# LAN9254_C_P1.net
KiCad netlist of a schematic drawn in Altium Designer
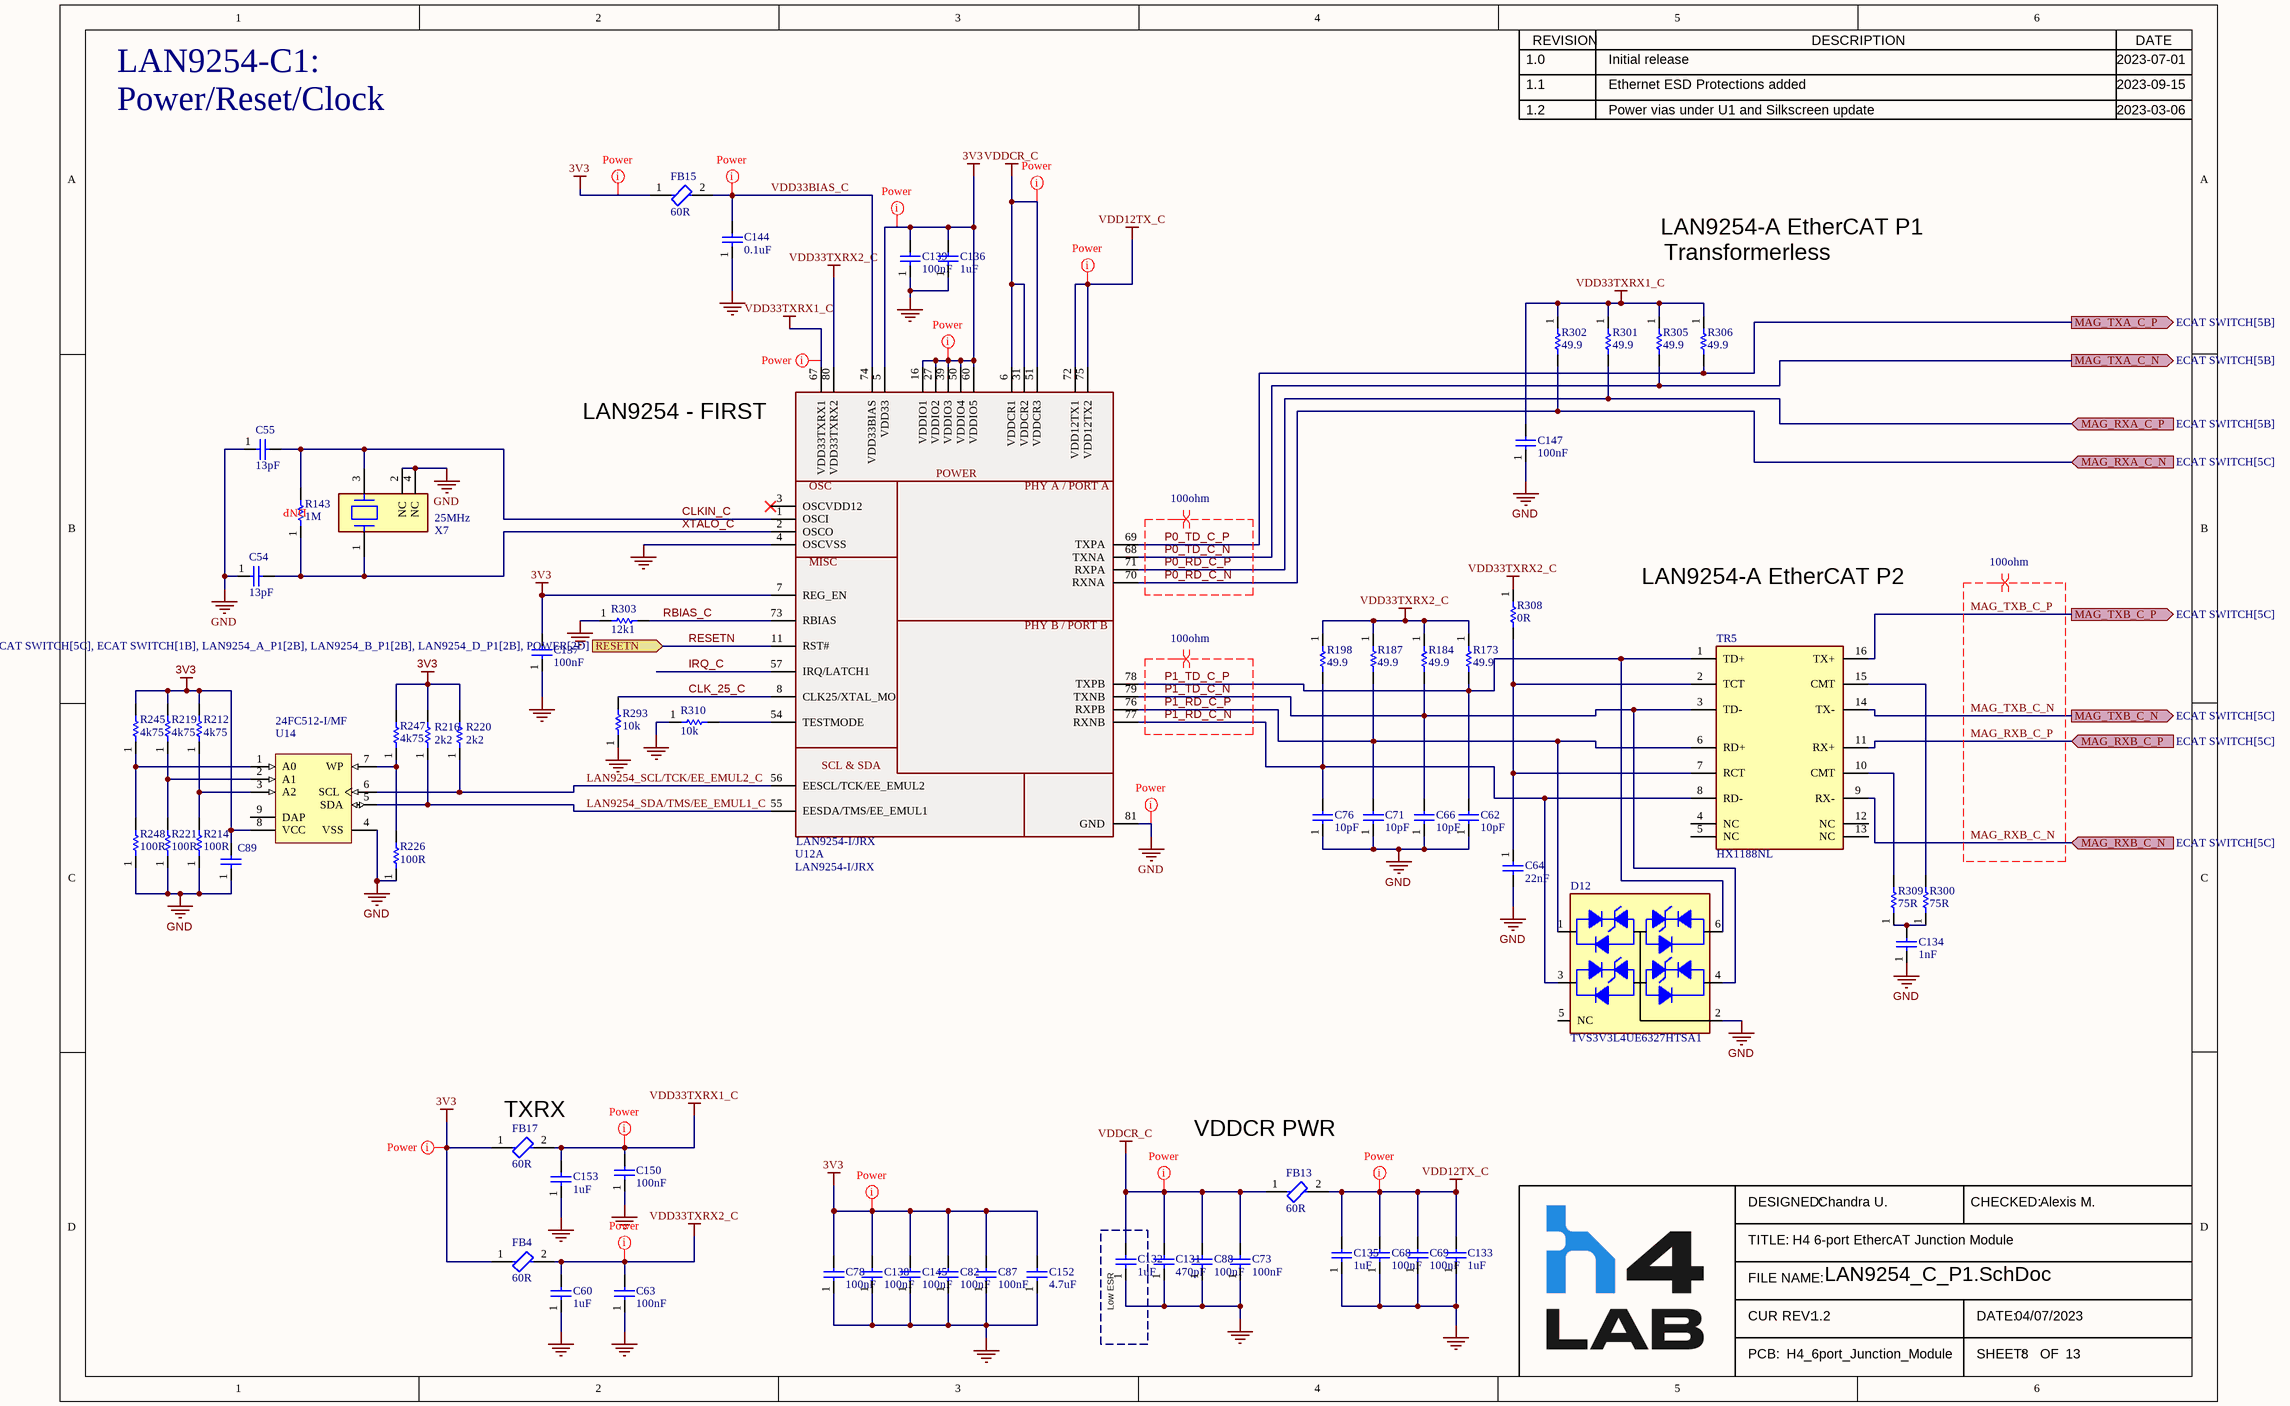
[diagram p0: LAN9254_C_P1.SchDoc]

(export (version "E")
  (design (tool "Eeschema 10.0.6"))
  (components
    (comp (ref "C54")
      (value "13pF")
      (footprint "0402_C")
      (description "Cap Ceramic Monolithic 13pF 50VDC 2% SMD Emboss T/R")
      (fields
        (field (name "MANUFACTURER") "Murata")
        (field (name "MANUFACTURER PART NUMBER") "GRM0225C1H130GA03L")
      )
      (libsource (lib "IHMC_Capacitors") (part "13pF_50V_0402_CAP_GRM0225C1H130GA03L"))
    )
    (comp (ref "C55")
      (value "13pF")
      (footprint "0402_C")
      (description "Cap Ceramic Monolithic 13pF 50VDC 2% SMD Emboss T/R")
      (fields
        (field (name "MANUFACTURER") "Murata")
        (field (name "MANUFACTURER PART NUMBER") "GRM0225C1H130GA03L")
      )
      (libsource (lib "IHMC_Capacitors") (part "13pF_50V_0402_CAP_GRM0225C1H130GA03L"))
    )
    (comp (ref "C60")
      (value "1uF")
      (footprint "CAPC1608X09N(0603)")
      (description "MLCC - SMD/SMT 25volts 1uF X5R 10%")
      (fields
        (field (name "MPN") "C0603C105K3PACTU")
        (field (name "VOLTAGE") "25VDC")
        (field (name "DRAWN BY") "TC")
      )
      (libsource (lib "IHMC_Altium_Lib") (part "1uF_25VDC_0603_Cap"))
    )
    (comp (ref "C62")
      (value "10pF")
      (footprint "0402_C")
      (description "Cap Ceramic 10pF 50V C0G 5% SMD 0402 125°C Punched Paper T/R")
      (fields (field (name "TOLERANCE") "5%") (field (name "MANUFACTURER") "KEMET"))
      (libsource (lib "IHMC_Altium_Lib") (part "10pF_50V_0402_C0402C100J5GAC7411"))
    )
    (comp (ref "C63")
      (value "100nF")
      (footprint "CAPC1005X03N(0402)")
      (description "CAP CER 0.1UF 16V X7R 0402")
      (fields (field (name "MPN") "GRM155R71C104JA88D") (field (name "TOLERANCE") "5%"))
      (libsource (lib "IHMC_Altium_Lib") (part "100nF_16V_0402_CAP"))
    )
    (comp (ref "C64")
      (value "22nF")
      (footprint "CAPC1005X03N(0402)")
      (description "CAP CER 0.022UF 50V X7R 0402")
      (fields (field (name "MPN") "GCM155R71H223KA55D") (field (name "TOLERANCE") "10%"))
      (libsource (lib "IHMC_Capacitors") (part "22nF_50V_0402_CAP"))
    )
    (comp (ref "C66")
      (value "10pF")
      (footprint "0402_C")
      (description "Cap Ceramic 10pF 50V C0G 5% SMD 0402 125°C Punched Paper T/R")
      (fields (field (name "TOLERANCE") "5%") (field (name "MANUFACTURER") "KEMET"))
      (libsource (lib "IHMC_Altium_Lib") (part "10pF_50V_0402_C0402C100J5GAC7411"))
    )
    (comp (ref "C68")
      (value "100nF")
      (footprint "CAPC1005X03N(0402)")
      (description "CAP CER 0.1UF 16V X7R 0402")
      (fields (field (name "MPN") "GRM155R71C104JA88D") (field (name "TOLERANCE") "5%"))
      (libsource (lib "IHMC_Altium_Lib") (part "100nF_16V_0402_CAP"))
    )
    (comp (ref "C69")
      (value "100nF")
      (footprint "CAPC1005X03N(0402)")
      (description "CAP CER 0.1UF 16V X7R 0402")
      (fields (field (name "MPN") "GRM155R71C104JA88D") (field (name "TOLERANCE") "5%"))
      (libsource (lib "IHMC_Altium_Lib") (part "100nF_16V_0402_CAP"))
    )
    (comp (ref "C71")
      (value "10pF")
      (footprint "0402_C")
      (description "Cap Ceramic 10pF 50V C0G 5% SMD 0402 125°C Punched Paper T/R")
      (fields (field (name "TOLERANCE") "5%") (field (name "MANUFACTURER") "KEMET"))
      (libsource (lib "IHMC_Altium_Lib") (part "10pF_50V_0402_C0402C100J5GAC7411"))
    )
    (comp (ref "C73")
      (value "100nF")
      (footprint "CAPC1005X03N(0402)")
      (description "CAP CER 0.1UF 16V X7R 0402")
      (fields (field (name "MPN") "GRM155R71C104JA88D") (field (name "TOLERANCE") "5%"))
      (libsource (lib "IHMC_Altium_Lib") (part "100nF_16V_0402_CAP"))
    )
    (comp (ref "C76")
      (value "10pF")
      (footprint "0402_C")
      (description "Cap Ceramic 10pF 50V C0G 5% SMD 0402 125°C Punched Paper T/R")
      (fields (field (name "TOLERANCE") "5%") (field (name "MANUFACTURER") "KEMET"))
      (libsource (lib "IHMC_Altium_Lib") (part "10pF_50V_0402_C0402C100J5GAC7411"))
    )
    (comp (ref "C78")
      (value "100nF")
      (footprint "CAPC1005X03N(0402)")
      (description "CAP CER 0.1UF 16V X7R 0402")
      (fields (field (name "MPN") "GRM155R71C104JA88D") (field (name "TOLERANCE") "5%"))
      (libsource (lib "IHMC_Altium_Lib") (part "100nF_16V_0402_CAP"))
    )
    (comp (ref "C82")
      (value "100nF")
      (footprint "CAPC1005X03N(0402)")
      (description "CAP CER 0.1UF 16V X7R 0402")
      (fields (field (name "MPN") "GRM155R71C104JA88D") (field (name "TOLERANCE") "5%"))
      (libsource (lib "IHMC_Altium_Lib") (part "100nF_16V_0402_CAP"))
    )
    (comp (ref "C87")
      (value "100nF")
      (footprint "CAPC1005X03N(0402)")
      (description "CAP CER 0.1UF 16V X7R 0402")
      (fields (field (name "MPN") "GRM155R71C104JA88D") (field (name "TOLERANCE") "5%"))
      (libsource (lib "IHMC_Altium_Lib") (part "100nF_16V_0402_CAP"))
    )
    (comp (ref "C88")
      (value "100nF")
      (footprint "CAPC1005X03N(0402)")
      (description "CAP CER 0.1UF 16V X7R 0402")
      (fields (field (name "MPN") "GRM155R71C104JA88D") (field (name "TOLERANCE") "5%"))
      (libsource (lib "IHMC_Altium_Lib") (part "100nF_16V_0402_CAP"))
    )
    (comp (ref "C89")
      (value "GRM155R71C104JA88D")
      (footprint "CAPC1005X03N(0402)")
      (description "CAP CER 0.1UF 16V X7R 0402")
      (fields (field (name "TOLERANCE") "5%"))
      (libsource (lib "IHMC_Altium_Lib") (part "100nF_16V_0402_CAP"))
    )
    (comp (ref "C131")
      (value "470pF")
      (footprint "CAPC1005X03N(0402)")
      (description "CAP CER 470PF 50V C0G/NP0 0402")
      (fields (field (name "MPN") "GCM1555C1H471JA16D") (field (name "VOLTAGE") "50V"))
      (libsource (lib "IHMC_Altium_Lib") (part "470pF_50V_0402_CAP"))
    )
    (comp (ref "C132")
      (value "1uF")
      (footprint "0603_C")
      (description "Multilayer Ceramic Capacitors (High dielectric type), 10V, 1 uF, ± 10 %, 0603, X5R, RoHS")
      (fields (field (name "TOLERANCE") "10%") (field (name "MANUFACTURER") "Taiyo Yuden"))
      (libsource (lib "IHMC_Capacitors") (part "1uF_10V_low_ESR_0603_LMK107BJ105KA-T"))
    )
    (comp (ref "C133")
      (value "1uF")
      (footprint "CAPC1608X09N(0603)")
      (description "MLCC - SMD/SMT 25volts 1uF X5R 10%")
      (fields
        (field (name "MPN") "C0603C105K3PACTU")
        (field (name "VOLTAGE") "25VDC")
        (field (name "DRAWN BY") "TC")
      )
      (libsource (lib "IHMC_Altium_Lib") (part "1uF_25VDC_0603_Cap"))
    )
    (comp (ref "C134")
      (value "1nF")
      (footprint "CAPC3216X16N(1206)")
      (description "CAP CER 1000PF 2KV X7R 1206")
      (fields (field (name "TOLERANCE") "10%") (field (name "MPN") "CC1206KKX7RDBB102"))
      (libsource (lib "IHMC_Altium_Lib") (part "1nF_2kV_1206_CAP"))
    )
    (comp (ref "C135")
      (value "1uF")
      (footprint "CAPC1608X09N(0603)")
      (description "MLCC - SMD/SMT 25volts 1uF X5R 10%")
      (fields
        (field (name "MPN") "C0603C105K3PACTU")
        (field (name "VOLTAGE") "25VDC")
        (field (name "DRAWN BY") "TC")
      )
      (libsource (lib "IHMC_Altium_Lib") (part "1uF_25VDC_0603_Cap"))
    )
    (comp (ref "C136")
      (value "1uF")
      (footprint "0603_C")
      (description "Multilayer Ceramic Capacitors (High dielectric type), 10V, 1 uF, ± 10 %, 0603, X5R, RoHS")
      (fields (field (name "TOLERANCE") "10%") (field (name "MANUFACTURER") "Taiyo Yuden"))
      (libsource (lib "IHMC_Capacitors") (part "1uF_10V_low_ESR_0603_LMK107BJ105KA-T"))
    )
    (comp (ref "C137")
      (value "100nF")
      (footprint "CAPC1005X03N(0402)")
      (description "CAP CER 0.1UF 16V X7R 0402")
      (fields (field (name "MPN") "GRM155R71C104JA88D") (field (name "TOLERANCE") "5%"))
      (libsource (lib "IHMC_Altium_Lib") (part "100nF_16V_0402_CAP"))
    )
    (comp (ref "C138")
      (value "100nF")
      (footprint "CAPC1005X03N(0402)")
      (description "CAP CER 0.1UF 16V X7R 0402")
      (fields (field (name "MPN") "GRM155R71C104JA88D") (field (name "TOLERANCE") "5%"))
      (libsource (lib "IHMC_Altium_Lib") (part "100nF_16V_0402_CAP"))
    )
    (comp (ref "C139")
      (value "100nF")
      (footprint "CAPC1005X03N(0402)")
      (description "CAP CER 0.1UF 16V X7R 0402")
      (fields (field (name "MPN") "GRM155R71C104JA88D") (field (name "TOLERANCE") "5%"))
      (libsource (lib "IHMC_Altium_Lib") (part "100nF_16V_0402_CAP"))
    )
    (comp (ref "C144")
      (value "0.1uF")
      (footprint "CAPC1608X09N(0603)")
      (description "CAP CER 0.1UF 100V X7R 0603")
      (fields (field (name "MPN") "CL10B104KC8NNNC") (field (name "TOLERANCE") "10%"))
      (libsource (lib "IHMC_Altium_Lib") (part "0.1uF_100V_0603_CAP"))
    )
    (comp (ref "C145")
      (value "100nF")
      (footprint "CAPC1005X03N(0402)")
      (description "CAP CER 0.1UF 16V X7R 0402")
      (fields (field (name "MPN") "GRM155R71C104JA88D") (field (name "TOLERANCE") "5%"))
      (libsource (lib "IHMC_Altium_Lib") (part "100nF_16V_0402_CAP"))
    )
    (comp (ref "C147")
      (value "100nF")
      (footprint "CAPC1005X03N(0402)")
      (description "CAP CER 0.1UF 16V X7R 0402")
      (fields (field (name "TOLERANCE") "5%") (field (name "MPN") "GRM155R71C104JA88D"))
      (libsource (lib "IHMC_Altium_Lib") (part "100nF_16V_0402_CAP"))
    )
    (comp (ref "C150")
      (value "100nF")
      (footprint "CAPC1005X03N(0402)")
      (description "CAP CER 0.1UF 16V X7R 0402")
      (fields (field (name "MPN") "GRM155R71C104JA88D") (field (name "TOLERANCE") "5%"))
      (libsource (lib "IHMC_Altium_Lib") (part "100nF_16V_0402_CAP"))
    )
    (comp (ref "C152")
      (value "4.7uF")
      (footprint "CAPC3216X16N(1206)")
      (description "CAP CER 4.7UF 50V X7R 1206")
      (fields (field (name "MPN") "CL31B475KBHNNNE") (field (name "TOLERANCE") "10%"))
      (libsource (lib "IHMC_Altium_Lib") (part "4.7uF_50V_1206_CAP"))
    )
    (comp (ref "C153")
      (value "1uF")
      (footprint "CAPC1608X09N(0603)")
      (description "MLCC - SMD/SMT 25volts 1uF X5R 10%")
      (fields
        (field (name "MPN") "C0603C105K3PACTU")
        (field (name "VOLTAGE") "25VDC")
        (field (name "DRAWN BY") "TC")
      )
      (libsource (lib "IHMC_Altium_Lib") (part "1uF_25VDC_0603_Cap"))
    )
    (comp (ref "D12")
      (value "TVS3V3L4UE6327HTSA1")
      (footprint "FP-SOT457-MFG")
      (description "Trans Voltage Suppressor Diode, 3.3V V(RWM), Unidirectional, 4 Element, Silicon")
      (fields (field (name "MANUFACTURER") "Infineon"))
      (libsource (lib "IHMC_Altium_Lib") (part "TVS_DIODE_ETHERCAT_PHY_7.7V_20A_TVS3V3L4UE6327HTSA1"))
    )
    (comp (ref "FB4")
      (value "BKP2125HS600-T")
      (footprint "FP-BKP2125-IPC_C")
      (fields
        (field (name "TOLERANCE") "25%")
        (field (name "MANUFACTURER") "Taiyo Yuden")
        (field (name "IMPEDANCE") "60R")
      )
      (libsource (lib "IHMC_Altium_Lib") (part "60R_100Mhz_0805_3A"))
    )
    (comp (ref "FB13")
      (value "BKP2125HS600-T")
      (footprint "FP-BKP2125-IPC_C")
      (fields
        (field (name "TOLERANCE") "25%")
        (field (name "MANUFACTURER") "Taiyo Yuden")
        (field (name "IMPEDANCE") "60R")
      )
      (libsource (lib "IHMC_Altium_Lib") (part "60R_100Mhz_0805_3A"))
    )
    (comp (ref "FB15")
      (value "BKP2125HS600-T")
      (footprint "FP-BKP2125-IPC_C")
      (fields
        (field (name "TOLERANCE") "25%")
        (field (name "MANUFACTURER") "Taiyo Yuden")
        (field (name "IMPEDANCE") "60R")
      )
      (libsource (lib "IHMC_Altium_Lib") (part "60R_100Mhz_0805_3A"))
    )
    (comp (ref "FB17")
      (value "BKP2125HS600-T")
      (footprint "FP-BKP2125-IPC_C")
      (fields
        (field (name "TOLERANCE") "25%")
        (field (name "MANUFACTURER") "Taiyo Yuden")
        (field (name "IMPEDANCE") "60R")
      )
      (libsource (lib "IHMC_Altium_Lib") (part "60R_100Mhz_0805_3A"))
    )
    (comp (ref "R143")
      (value "1M")
      (footprint "RESC1608X09N(0603)")
      (description "RES SMD 1M OHM 1% 1/10W 0603")
      (fields (field (name "MPN") "RC0603FR-071ML") (field (name "TOLERANCE") "1%"))
      (libsource (lib "IHMC_Altium_Lib") (part "1M_1/10W_RES_0603"))
    )
    (comp (ref "R173")
      (value "49.9")
      (footprint "RESC1005X06N(0402)")
      (description "RES SMD 49.9 OHM 1% 1/16W 0402")
      (fields
        (field (name "MPN") "CRCW040249R9FKED")
        (field (name "TOLERANCE") "1%")
        (field (name "DRAWN BY") "TC")
      )
      (libsource (lib "IHMC_Altium_Lib") (part "49R9_1/10W_0402_RES"))
    )
    (comp (ref "R184")
      (value "49.9")
      (footprint "RESC1005X06N(0402)")
      (description "RES SMD 49.9 OHM 1% 1/16W 0402")
      (fields
        (field (name "MPN") "CRCW040249R9FKED")
        (field (name "TOLERANCE") "1%")
        (field (name "DRAWN BY") "TC")
      )
      (libsource (lib "IHMC_Altium_Lib") (part "49R9_1/10W_0402_RES"))
    )
    (comp (ref "R187")
      (value "49.9")
      (footprint "RESC1005X06N(0402)")
      (description "RES SMD 49.9 OHM 1% 1/16W 0402")
      (fields
        (field (name "MPN") "CRCW040249R9FKED")
        (field (name "TOLERANCE") "1%")
        (field (name "DRAWN BY") "TC")
      )
      (libsource (lib "IHMC_Altium_Lib") (part "49R9_1/10W_0402_RES"))
    )
    (comp (ref "R198")
      (value "49.9")
      (footprint "RESC1005X06N(0402)")
      (description "RES SMD 49.9 OHM 1% 1/16W 0402")
      (fields
        (field (name "MPN") "CRCW040249R9FKED")
        (field (name "TOLERANCE") "1%")
        (field (name "DRAWN BY") "TC")
      )
      (libsource (lib "IHMC_Altium_Lib") (part "49R9_1/10W_0402_RES"))
    )
    (comp (ref "R212")
      (value "4k75")
      (footprint "RESC1005X06N(0402)")
      (description "RES SMD 4.75K OHM 1% 1/16W 0402")
      (fields (field (name "MPN") "RC0402FR-074K75L") (field (name "POWER") "1/16"))
      (libsource (lib "IHMC_Altium_Lib") (part "4k75_1/16_0402_RES"))
    )
    (comp (ref "R214")
      (value "100R")
      (footprint "0402")
      (description "Res Thick Film 0402 100 Ohm 1% 0.063W(1/16W) ±200ppm/C Pad SMD Automotive T/R")
      (fields
        (field (name "MANUFACTURER") "TE Connectivity")
        (field (name "MANUFACTURER PART NUMBER") "CRGCQ0402F100R")
      )
      (libsource (lib "IHMC_Altium_Lib") (part "100R_1/16_0402_RES"))
    )
    (comp (ref "R216")
      (value "2k2")
      (footprint "0402")
      (description "Vishay CRCW Series Thick Film Resistor 0402 Case 2.2k 5% 0.063W 200ppm/K")
      (fields (field (name "TOLERANCE") "5%") (field (name "MANUFACTURER") "Vishay Dale"))
      (libsource (lib "IHMC_Altium_Lib") (part "2k2_1/16_0402_CRCW04022K20JNED_RES"))
    )
    (comp (ref "R219")
      (value "4k75")
      (footprint "RESC1005X06N(0402)")
      (description "RES SMD 4.75K OHM 1% 1/16W 0402")
      (fields (field (name "MPN") "RC0402FR-074K75L") (field (name "POWER") "1/16"))
      (libsource (lib "IHMC_Altium_Lib") (part "4k75_1/16_0402_RES"))
    )
    (comp (ref "R220")
      (value "2k2")
      (footprint "0402")
      (description "Vishay CRCW Series Thick Film Resistor 0402 Case 2.2k 5% 0.063W 200ppm/K")
      (fields (field (name "TOLERANCE") "5%") (field (name "MANUFACTURER") "Vishay Dale"))
      (libsource (lib "IHMC_Altium_Lib") (part "2k2_1/16_0402_CRCW04022K20JNED_RES"))
    )
    (comp (ref "R221")
      (value "100R")
      (footprint "0402")
      (description "Res Thick Film 0402 100 Ohm 1% 0.063W(1/16W) ±200ppm/C Pad SMD Automotive T/R")
      (fields
        (field (name "MANUFACTURER") "TE Connectivity")
        (field (name "MANUFACTURER PART NUMBER") "CRGCQ0402F100R")
      )
      (libsource (lib "IHMC_Altium_Lib") (part "100R_1/16_0402_RES"))
    )
    (comp (ref "R226")
      (value "100R")
      (footprint "0402")
      (description "Res Thick Film 0402 100 Ohm 1% 0.063W(1/16W) ±200ppm/C Pad SMD Automotive T/R")
      (fields
        (field (name "MANUFACTURER") "TE Connectivity")
        (field (name "MANUFACTURER PART NUMBER") "CRGCQ0402F100R")
      )
      (libsource (lib "IHMC_Altium_Lib") (part "100R_1/16_0402_RES"))
    )
    (comp (ref "R245")
      (value "4k75")
      (footprint "RESC1005X06N(0402)")
      (description "RES SMD 4.75K OHM 1% 1/16W 0402")
      (fields (field (name "MPN") "RC0402FR-074K75L") (field (name "POWER") "1/16"))
      (libsource (lib "IHMC_Altium_Lib") (part "4k75_1/16_0402_RES"))
    )
    (comp (ref "R247")
      (value "4k75")
      (footprint "RESC1005X06N(0402)")
      (description "RES SMD 4.75K OHM 1% 1/16W 0402")
      (fields (field (name "MPN") "RC0402FR-074K75L") (field (name "POWER") "1/16"))
      (libsource (lib "IHMC_Altium_Lib") (part "4k75_1/16_0402_RES"))
    )
    (comp (ref "R248")
      (value "100R")
      (footprint "0402")
      (description "Res Thick Film 0402 100 Ohm 1% 0.063W(1/16W) ±200ppm/C Pad SMD Automotive T/R")
      (fields
        (field (name "MANUFACTURER") "TE Connectivity")
        (field (name "MANUFACTURER PART NUMBER") "CRGCQ0402F100R")
      )
      (libsource (lib "IHMC_Altium_Lib") (part "100R_1/16_0402_RES"))
    )
    (comp (ref "R293")
      (value "10k")
      (footprint "RESC1005X06N(0402)")
      (description "RES SMD 10K OHM 1% 1/16W 0402")
      (fields (field (name "TOLERANCE") "1%") (field (name "POWER") "1/16W"))
      (libsource (lib "IHMC_Resistors") (part "10k_1/16W_0402_RES"))
    )
    (comp (ref "R300")
      (value "75R")
      (footprint "RESC1005X06N(0402)")
      (description "RES SMD 75 OHM 1% 1/16W 0402")
      (fields
        (field (name "MPN") "CRCW040275R0FKEDC")
        (field (name "TOLERANCE") "+/-1%")
        (field (name "DRAWN BY") "TC")
      )
      (libsource (lib "IHMC_Altium_Lib") (part "75R_1/10W_0402_RES"))
    )
    (comp (ref "R301")
      (value "49.9")
      (footprint "RESC1005X06N(0402)")
      (description "RES SMD 49.9 OHM 1% 1/16W 0402")
      (fields
        (field (name "MPN") "CRCW040249R9FKED")
        (field (name "TOLERANCE") "1%")
        (field (name "DRAWN BY") "TC")
      )
      (libsource (lib "IHMC_Altium_Lib") (part "49R9_1/10W_0402_RES"))
    )
    (comp (ref "R302")
      (value "49.9")
      (footprint "RESC1005X06N(0402)")
      (description "RES SMD 49.9 OHM 1% 1/16W 0402")
      (fields
        (field (name "MPN") "CRCW040249R9FKED")
        (field (name "TOLERANCE") "1%")
        (field (name "DRAWN BY") "TC")
      )
      (libsource (lib "IHMC_Altium_Lib") (part "49R9_1/10W_0402_RES"))
    )
    (comp (ref "R303")
      (value "12k1")
      (footprint "RESC1005X06N(0402)")
      (description "RES SMD 12.1K OHM 1% 1/16W 0402")
      (fields (field (name "MPN") "RC0402FR-0712K1L") (field (name "TOLERANCE") "1%"))
      (libsource (lib "IHMC_Altium_Lib") (part "12k1_1/16W-0402_RES"))
    )
    (comp (ref "R305")
      (value "49.9")
      (footprint "RESC1005X06N(0402)")
      (description "RES SMD 49.9 OHM 1% 1/16W 0402")
      (fields
        (field (name "MPN") "CRCW040249R9FKED")
        (field (name "TOLERANCE") "1%")
        (field (name "DRAWN BY") "TC")
      )
      (libsource (lib "IHMC_Altium_Lib") (part "49R9_1/10W_0402_RES"))
    )
    (comp (ref "R306")
      (value "49.9")
      (footprint "RESC1005X06N(0402)")
      (description "RES SMD 49.9 OHM 1% 1/16W 0402")
      (fields
        (field (name "MPN") "CRCW040249R9FKED")
        (field (name "TOLERANCE") "1%")
        (field (name "DRAWN BY") "TC")
      )
      (libsource (lib "IHMC_Altium_Lib") (part "49R9_1/10W_0402_RES"))
    )
    (comp (ref "R308")
      (value "0R")
      (footprint "0402")
      (fields
        (field (name "MANUFACTURER") "Vishay Dale")
        (field (name "MANUFACTURER PART NUMBER") "RCS04020000Z0ED")
      )
      (libsource (lib "IHMC_Altium_Lib") (part "0R_1/5W_0402_RCS04020000Z0ED_RES"))
    )
    (comp (ref "R309")
      (value "75R")
      (footprint "RESC1005X06N(0402)")
      (description "RES SMD 75 OHM 1% 1/16W 0402")
      (fields
        (field (name "MPN") "CRCW040275R0FKEDC")
        (field (name "TOLERANCE") "+/-1%")
        (field (name "DRAWN BY") "TC")
      )
      (libsource (lib "IHMC_Altium_Lib") (part "75R_1/10W_0402_RES"))
    )
    (comp (ref "R310")
      (value "10k")
      (footprint "RESC1005X06N(0402)")
      (description "RES SMD 10K OHM 1% 1/16W 0402")
      (fields (field (name "TOLERANCE") "1%") (field (name "POWER") "1/16W"))
      (libsource (lib "IHMC_Resistors") (part "10k_1/16W_0402_RES"))
    )
    (comp (ref "TR5")
      (value "HX1188NL")
      (footprint "FP-HX1188NL-MFG")
      (description "Datacom Transformer, GENERAL PURPOSE Application(s), 1:1; 1:1")
      (fields (field (name "MANUFACTURER") "Pulse"))
      (libsource (lib "IHMC_Ethernet") (part "HX1188NL_TRANSFO_LAN_-40-85DEG"))
    )
    (comp (ref "U12")
      (value "LAN9254-I/JRX")
      (footprint "QFP50P1400X1400X120-81N")
      (description "2/3-PORT Ethercat Slave Controller With 32 Digios With Integrated Ethernet Phys")
      (fields (field (name "MANUFACTURER") "Microchip"))
      (libsource (lib "IHMC_Ethernet") (part "LAN9254-I/JRX"))
    )
    (comp (ref "U14")
      (value "24FC512-I/MF")
      (footprint "DFNS-MF8")
      (description "EEPROM Serial-2Wire 512K-bit 64K x 8 1.8V/2.5V/3.3V/5V 8-Pin DFN-S EP Tube")
      (fields (field (name "MANUFACTURER") "Microchip"))
      (libsource (lib "IHMC_Altium_Lib") (part "EEPROM_512kb_1MHz_24FC512-I/MF"))
    )
    (comp (ref "X7")
      (value "XRCGB25M000F3A00R0")
      (footprint "FP-XRCGB-MFG")
      (description "Crystal 25MHz ±30ppm (Tol) ±35ppm (Stability) 6pF 100Ohm Automotive 4-Pin SMD T/R")
      (fields (field (name "FREQUENCY") "25MHz") (field (name "MANUFACTURER") "Murata"))
      (libsource (lib "IHMC_Altium_Lib") (part "25MHz_Crystal_2016_35PPM_XRCGB25M000F3A00R0"))
    )
  )
  (nets
    (net (code "1") (name "/CLKIN_C") (class "Default")
      (node (ref "C55") (pin "2") (pinfunction "2_2") (pintype "passive"))
      (node (ref "R143") (pin "2") (pinfunction "2_2") (pintype "passive"))
      (node (ref "U12") (pin "1") (pinfunction "OSCI_1") (pintype "passive"))
      (node (ref "X7") (pin "3") (pintype "passive"))
    )
    (net (code "2") (name "/CLK_25_C") (class "Default")
      (node (ref "R293") (pin "2") (pinfunction "2_2") (pintype "passive"))
      (node (ref "U12") (pin "8") (pinfunction "CLK25/XTAL_MO_8") (pintype "passive"))
    )
    (net (code "3") (name "/IRQ_C") (class "Default")
      (node (ref "U12") (pin "57") (pinfunction "IRQ/LATCH1_57") (pintype "passive"))
    )
    (net (code "4") (name "/LAN9254_SCL{slash}TCK{slash}EE_EMUL2_C") (class "Default")
      (node (ref "R220") (pin "1") (pinfunction "1_1") (pintype "passive"))
      (node (ref "U12") (pin "56") (pinfunction "EESCL/TCK/EE_EMUL2_56") (pintype "passive"))
      (node (ref "U14") (pin "6") (pinfunction "SCL_6") (pintype "input"))
    )
    (net (code "5") (name "/LAN9254_SDA{slash}TMS{slash}EE_EMUL1_C") (class "Default")
      (node (ref "R216") (pin "1") (pinfunction "1_1") (pintype "passive"))
      (node (ref "U12") (pin "55") (pinfunction "EESDA/TMS/EE_EMUL1_55") (pintype "passive"))
      (node (ref "U14") (pin "5") (pinfunction "SDA_5") (pintype "bidirectional"))
    )
    (net (code "6") (name "/MAG_RXB_C_N") (class "Default")
      (node (ref "TR5") (pin "9") (pinfunction "RX-_9") (pintype "passive"))
    )
    (net (code "7") (name "/MAG_RXB_C_P") (class "Default")
      (node (ref "TR5") (pin "11") (pinfunction "RX+_11") (pintype "passive"))
    )
    (net (code "8") (name "/MAG_TXB_C_N") (class "Default")
      (node (ref "TR5") (pin "14") (pinfunction "TX-_14") (pintype "passive"))
    )
    (net (code "9") (name "/MAG_TXB_C_P") (class "Default")
      (node (ref "TR5") (pin "16") (pinfunction "TX+_16") (pintype "passive"))
    )
    (net (code "10") (name "/P0_RD_C_N") (class "Default")
      (node (ref "R302") (pin "2") (pinfunction "2_2") (pintype "passive"))
      (node (ref "U12") (pin "70") (pinfunction "RXNA_70") (pintype "passive"))
    )
    (net (code "11") (name "/P0_RD_C_P") (class "Default")
      (node (ref "R301") (pin "2") (pinfunction "2_2") (pintype "passive"))
      (node (ref "U12") (pin "71") (pinfunction "RXPA_71") (pintype "passive"))
    )
    (net (code "12") (name "/P0_TD_C_N") (class "Default")
      (node (ref "R305") (pin "2") (pinfunction "2_2") (pintype "passive"))
      (node (ref "U12") (pin "68") (pinfunction "TXNA_68") (pintype "passive"))
    )
    (net (code "13") (name "/P0_TD_C_P") (class "Default")
      (node (ref "R306") (pin "2") (pinfunction "2_2") (pintype "passive"))
      (node (ref "U12") (pin "69") (pinfunction "TXPA_69") (pintype "passive"))
    )
    (net (code "14") (name "/P1_RD_C_N") (class "Default")
      (node (ref "C76") (pin "2") (pinfunction "2_2") (pintype "passive"))
      (node (ref "D12") (pin "3") (pinfunction "3_3") (pintype "passive"))
      (node (ref "R198") (pin "2") (pinfunction "2_2") (pintype "passive"))
      (node (ref "TR5") (pin "8") (pinfunction "RD-_8") (pintype "passive"))
      (node (ref "U12") (pin "77") (pinfunction "RXNB_77") (pintype "passive"))
    )
    (net (code "15") (name "/P1_RD_C_P") (class "Default")
      (node (ref "C71") (pin "2") (pinfunction "2_2") (pintype "passive"))
      (node (ref "D12") (pin "1") (pinfunction "1_1") (pintype "passive"))
      (node (ref "R187") (pin "2") (pinfunction "2_2") (pintype "passive"))
      (node (ref "TR5") (pin "6") (pinfunction "RD+_6") (pintype "passive"))
      (node (ref "U12") (pin "76") (pinfunction "RXPB_76") (pintype "passive"))
    )
    (net (code "16") (name "/P1_TD_C_N") (class "Default")
      (node (ref "C66") (pin "2") (pinfunction "2_2") (pintype "passive"))
      (node (ref "D12") (pin "4") (pinfunction "4_4") (pintype "passive"))
      (node (ref "R184") (pin "2") (pinfunction "2_2") (pintype "passive"))
      (node (ref "TR5") (pin "3") (pinfunction "TD-_3") (pintype "passive"))
      (node (ref "U12") (pin "79") (pinfunction "TXNB_79") (pintype "passive"))
    )
    (net (code "17") (name "/P1_TD_C_P") (class "Default")
      (node (ref "C62") (pin "2") (pinfunction "2_2") (pintype "passive"))
      (node (ref "D12") (pin "6") (pinfunction "6_6") (pintype "passive"))
      (node (ref "R173") (pin "2") (pinfunction "2_2") (pintype "passive"))
      (node (ref "TR5") (pin "1") (pinfunction "TD+_1") (pintype "passive"))
      (node (ref "U12") (pin "78") (pinfunction "TXPB_78") (pintype "passive"))
    )
    (net (code "18") (name "/RBIAS_C") (class "Default")
      (node (ref "R303") (pin "2") (pinfunction "2_2") (pintype "passive"))
      (node (ref "U12") (pin "73") (pinfunction "RBIAS_73") (pintype "passive"))
    )
    (net (code "19") (name "/RESETN") (class "Default")
      (node (ref "U12") (pin "11") (pinfunction "RST#_11") (pintype "passive"))
    )
    (net (code "20") (name "/VDD33BIAS_C") (class "Default")
      (node (ref "C144") (pin "2") (pinfunction "2_2") (pintype "passive"))
      (node (ref "FB15") (pin "2") (pinfunction "2_2") (pintype "passive"))
      (node (ref "U12") (pin "74") (pinfunction "VDD33BIAS_74") (pintype "passive"))
    )
    (net (code "21") (name "/XTALO_C") (class "Default")
      (node (ref "C54") (pin "2") (pinfunction "2_2") (pintype "passive"))
      (node (ref "R143") (pin "1") (pinfunction "1_1") (pintype "passive"))
      (node (ref "U12") (pin "2") (pinfunction "OSCO_2") (pintype "passive"))
      (node (ref "X7") (pin "1") (pintype "passive"))
    )
    (net (code "22") (name "3V3") (class "Default")
      (node (ref "C136") (pin "2") (pinfunction "2_2") (pintype "passive"))
      (node (ref "C137") (pin "2") (pinfunction "2_2") (pintype "passive"))
      (node (ref "C138") (pin "2") (pinfunction "2_2") (pintype "passive"))
      (node (ref "C139") (pin "2") (pinfunction "2_2") (pintype "passive"))
      (node (ref "C145") (pin "2") (pinfunction "2_2") (pintype "passive"))
      (node (ref "C152") (pin "2") (pinfunction "2_2") (pintype "passive"))
      (node (ref "C78") (pin "2") (pinfunction "2_2") (pintype "passive"))
      (node (ref "C82") (pin "2") (pinfunction "2_2") (pintype "passive"))
      (node (ref "C87") (pin "2") (pinfunction "2_2") (pintype "passive"))
      (node (ref "C89") (pin "2") (pinfunction "2_2") (pintype "passive"))
      (node (ref "FB15") (pin "1") (pinfunction "1_1") (pintype "passive"))
      (node (ref "FB17") (pin "1") (pinfunction "1_1") (pintype "passive"))
      (node (ref "FB4") (pin "1") (pinfunction "1_1") (pintype "passive"))
      (node (ref "R212") (pin "2") (pinfunction "2_2") (pintype "passive"))
      (node (ref "R216") (pin "2") (pinfunction "2_2") (pintype "passive"))
      (node (ref "R219") (pin "2") (pinfunction "2_2") (pintype "passive"))
      (node (ref "R220") (pin "2") (pinfunction "2_2") (pintype "passive"))
      (node (ref "R245") (pin "2") (pinfunction "2_2") (pintype "passive"))
      (node (ref "R247") (pin "2") (pinfunction "2_2") (pintype "passive"))
      (node (ref "U12") (pin "16") (pinfunction "VDDIO1_16") (pintype "passive"))
      (node (ref "U12") (pin "27") (pinfunction "VDDIO2_27") (pintype "passive"))
      (node (ref "U12") (pin "39") (pinfunction "VDDIO3_39") (pintype "passive"))
      (node (ref "U12") (pin "5") (pinfunction "VDD33_5") (pintype "passive"))
      (node (ref "U12") (pin "50") (pinfunction "VDDIO4_50") (pintype "passive"))
      (node (ref "U12") (pin "60") (pinfunction "VDDIO5_60") (pintype "passive"))
      (node (ref "U12") (pin "7") (pinfunction "REG_EN_7") (pintype "passive"))
      (node (ref "U14") (pin "8") (pinfunction "VCC_8") (pintype "power_in"))
    )
    (net (code "23") (name "GND") (class "Default")
      (node (ref "C131") (pin "1") (pinfunction "1_1") (pintype "passive"))
      (node (ref "C132") (pin "1") (pinfunction "1_1") (pintype "passive"))
      (node (ref "C133") (pin "1") (pinfunction "1_1") (pintype "passive"))
      (node (ref "C134") (pin "1") (pinfunction "1_1") (pintype "passive"))
      (node (ref "C135") (pin "1") (pinfunction "1_1") (pintype "passive"))
      (node (ref "C136") (pin "1") (pinfunction "1_1") (pintype "passive"))
      (node (ref "C137") (pin "1") (pinfunction "1_1") (pintype "passive"))
      (node (ref "C138") (pin "1") (pinfunction "1_1") (pintype "passive"))
      (node (ref "C139") (pin "1") (pinfunction "1_1") (pintype "passive"))
      (node (ref "C144") (pin "1") (pinfunction "1_1") (pintype "passive"))
      (node (ref "C145") (pin "1") (pinfunction "1_1") (pintype "passive"))
      (node (ref "C147") (pin "1") (pinfunction "1_1") (pintype "passive"))
      (node (ref "C150") (pin "1") (pinfunction "1_1") (pintype "passive"))
      (node (ref "C152") (pin "1") (pinfunction "1_1") (pintype "passive"))
      (node (ref "C153") (pin "1") (pinfunction "1_1") (pintype "passive"))
      (node (ref "C54") (pin "1") (pinfunction "1_1") (pintype "passive"))
      (node (ref "C55") (pin "1") (pinfunction "1_1") (pintype "passive"))
      (node (ref "C60") (pin "1") (pinfunction "1_1") (pintype "passive"))
      (node (ref "C62") (pin "1") (pinfunction "1_1") (pintype "passive"))
      (node (ref "C63") (pin "1") (pinfunction "1_1") (pintype "passive"))
      (node (ref "C64") (pin "2") (pinfunction "2_2") (pintype "passive"))
      (node (ref "C66") (pin "1") (pinfunction "1_1") (pintype "passive"))
      (node (ref "C68") (pin "1") (pinfunction "1_1") (pintype "passive"))
      (node (ref "C69") (pin "1") (pinfunction "1_1") (pintype "passive"))
      (node (ref "C71") (pin "1") (pinfunction "1_1") (pintype "passive"))
      (node (ref "C73") (pin "1") (pinfunction "1_1") (pintype "passive"))
      (node (ref "C76") (pin "1") (pinfunction "1_1") (pintype "passive"))
      (node (ref "C78") (pin "1") (pinfunction "1_1") (pintype "passive"))
      (node (ref "C82") (pin "1") (pinfunction "1_1") (pintype "passive"))
      (node (ref "C87") (pin "1") (pinfunction "1_1") (pintype "passive"))
      (node (ref "C88") (pin "1") (pinfunction "1_1") (pintype "passive"))
      (node (ref "C89") (pin "1") (pinfunction "1_1") (pintype "passive"))
      (node (ref "D12") (pin "2") (pinfunction "GND_2") (pintype "power_in"))
      (node (ref "R214") (pin "1") (pinfunction "1_1") (pintype "passive"))
      (node (ref "R221") (pin "1") (pinfunction "1_1") (pintype "passive"))
      (node (ref "R226") (pin "1") (pinfunction "1_1") (pintype "passive"))
      (node (ref "R248") (pin "1") (pinfunction "1_1") (pintype "passive"))
      (node (ref "R293") (pin "1") (pinfunction "1_1") (pintype "passive"))
      (node (ref "R303") (pin "1") (pinfunction "1_1") (pintype "passive"))
      (node (ref "R310") (pin "1") (pinfunction "1_1") (pintype "passive"))
      (node (ref "U12") (pin "4") (pinfunction "OSCVSS_4") (pintype "passive"))
      (node (ref "U12") (pin "81") (pinfunction "GND_81") (pintype "passive"))
      (node (ref "U14") (pin "4") (pinfunction "VSS_4") (pintype "power_in"))
      (node (ref "X7") (pin "2") (pinfunction "NC_2") (pintype "passive"))
      (node (ref "X7") (pin "4") (pinfunction "NC_4") (pintype "passive"))
    )
    (net (code "24") (name "Net-(C134-Pad2)") (class "Default")
      (node (ref "C134") (pin "2") (pinfunction "2_2") (pintype "passive"))
      (node (ref "R300") (pin "1") (pinfunction "1_1") (pintype "passive"))
      (node (ref "R309") (pin "1") (pinfunction "1_1") (pintype "passive"))
    )
    (net (code "25") (name "Net-(R300-Pad2)") (class "Default")
      (node (ref "R300") (pin "2") (pinfunction "2_2") (pintype "passive"))
      (node (ref "TR5") (pin "15") (pinfunction "CMT_15") (pintype "passive"))
    )
    (net (code "26") (name "Net-(R309-Pad2)") (class "Default")
      (node (ref "R309") (pin "2") (pinfunction "2_2") (pintype "passive"))
      (node (ref "TR5") (pin "10") (pinfunction "CMT_10") (pintype "passive"))
    )
    (net (code "27") (name "Net-(TR5-RCT)") (class "Default")
      (node (ref "C64") (pin "1") (pinfunction "1_1") (pintype "passive"))
      (node (ref "R308") (pin "2") (pinfunction "2_2") (pintype "passive"))
      (node (ref "TR5") (pin "2") (pinfunction "TCT_2") (pintype "passive"))
      (node (ref "TR5") (pin "7") (pinfunction "RCT_7") (pintype "passive"))
    )
    (net (code "28") (name "Net-(U12A-TESTMODE)") (class "Default")
      (node (ref "R310") (pin "2") (pinfunction "2_2") (pintype "passive"))
      (node (ref "U12") (pin "54") (pinfunction "TESTMODE_54") (pintype "passive"))
    )
    (net (code "29") (name "Net-(U14-A0)") (class "Default")
      (node (ref "R245") (pin "1") (pinfunction "1_1") (pintype "passive"))
      (node (ref "R248") (pin "2") (pinfunction "2_2") (pintype "passive"))
      (node (ref "U14") (pin "1") (pinfunction "A0_1") (pintype "input"))
    )
    (net (code "30") (name "Net-(U14-A1)") (class "Default")
      (node (ref "R219") (pin "1") (pinfunction "1_1") (pintype "passive"))
      (node (ref "R221") (pin "2") (pinfunction "2_2") (pintype "passive"))
      (node (ref "U14") (pin "2") (pinfunction "A1_2") (pintype "input"))
    )
    (net (code "31") (name "Net-(U14-A2)") (class "Default")
      (node (ref "R212") (pin "1") (pinfunction "1_1") (pintype "passive"))
      (node (ref "R214") (pin "2") (pinfunction "2_2") (pintype "passive"))
      (node (ref "U14") (pin "3") (pinfunction "A2_3") (pintype "input"))
    )
    (net (code "32") (name "Net-(U14-WP)") (class "Default")
      (node (ref "R226") (pin "2") (pinfunction "2_2") (pintype "passive"))
      (node (ref "R247") (pin "1") (pinfunction "1_1") (pintype "passive"))
      (node (ref "U14") (pin "7") (pinfunction "WP_7") (pintype "input"))
    )
    (net (code "33") (name "VDD12TX_C") (class "Default")
      (node (ref "C133") (pin "2") (pinfunction "2_2") (pintype "passive"))
      (node (ref "C135") (pin "2") (pinfunction "2_2") (pintype "passive"))
      (node (ref "C68") (pin "2") (pinfunction "2_2") (pintype "passive"))
      (node (ref "C69") (pin "2") (pinfunction "2_2") (pintype "passive"))
      (node (ref "FB13") (pin "2") (pinfunction "2_2") (pintype "passive"))
      (node (ref "U12") (pin "72") (pinfunction "VDD12TX1_72") (pintype "passive"))
      (node (ref "U12") (pin "75") (pinfunction "VDD12TX2_75") (pintype "passive"))
    )
    (net (code "34") (name "VDD33TXRX1_C") (class "Default")
      (node (ref "C147") (pin "2") (pinfunction "2_2") (pintype "passive"))
      (node (ref "C150") (pin "2") (pinfunction "2_2") (pintype "passive"))
      (node (ref "C153") (pin "2") (pinfunction "2_2") (pintype "passive"))
      (node (ref "FB17") (pin "2") (pinfunction "2_2") (pintype "passive"))
      (node (ref "R301") (pin "1") (pinfunction "1_1") (pintype "passive"))
      (node (ref "R302") (pin "1") (pinfunction "1_1") (pintype "passive"))
      (node (ref "R305") (pin "1") (pinfunction "1_1") (pintype "passive"))
      (node (ref "R306") (pin "1") (pinfunction "1_1") (pintype "passive"))
      (node (ref "U12") (pin "67") (pinfunction "VDD33TXRX1_67") (pintype "passive"))
    )
    (net (code "35") (name "VDD33TXRX2_C") (class "Default")
      (node (ref "C60") (pin "2") (pinfunction "2_2") (pintype "passive"))
      (node (ref "C63") (pin "2") (pinfunction "2_2") (pintype "passive"))
      (node (ref "FB4") (pin "2") (pinfunction "2_2") (pintype "passive"))
      (node (ref "R173") (pin "1") (pinfunction "1_1") (pintype "passive"))
      (node (ref "R184") (pin "1") (pinfunction "1_1") (pintype "passive"))
      (node (ref "R187") (pin "1") (pinfunction "1_1") (pintype "passive"))
      (node (ref "R198") (pin "1") (pinfunction "1_1") (pintype "passive"))
      (node (ref "R308") (pin "1") (pinfunction "1_1") (pintype "passive"))
      (node (ref "U12") (pin "80") (pinfunction "VDD33TXRX2_80") (pintype "passive"))
    )
    (net (code "36") (name "VDDCR_C") (class "Default")
      (node (ref "C131") (pin "2") (pinfunction "2_2") (pintype "passive"))
      (node (ref "C132") (pin "2") (pinfunction "2_2") (pintype "passive"))
      (node (ref "C73") (pin "2") (pinfunction "2_2") (pintype "passive"))
      (node (ref "C88") (pin "2") (pinfunction "2_2") (pintype "passive"))
      (node (ref "FB13") (pin "1") (pinfunction "1_1") (pintype "passive"))
      (node (ref "U12") (pin "31") (pinfunction "VDDCR2_31") (pintype "passive"))
      (node (ref "U12") (pin "51") (pinfunction "VDDCR3_51") (pintype "passive"))
      (node (ref "U12") (pin "6") (pinfunction "VDDCR1_6") (pintype "passive"))
    )
    (net (code "37") (name "unconnected-(D12-NC-Pad5)") (class "Default")
      (node (ref "D12") (pin "5") (pinfunction "NC_5") (pintype "passive"))
    )
    (net (code "38") (name "unconnected-(TR5-NC-Pad4)") (class "Default")
      (node (ref "TR5") (pin "4") (pinfunction "NC_4") (pintype "passive"))
    )
    (net (code "39") (name "unconnected-(TR5-NC-Pad5)") (class "Default")
      (node (ref "TR5") (pin "5") (pinfunction "NC_5") (pintype "passive"))
    )
    (net (code "40") (name "unconnected-(TR5-NC-Pad12)") (class "Default")
      (node (ref "TR5") (pin "12") (pinfunction "NC_12") (pintype "passive"))
    )
    (net (code "41") (name "unconnected-(TR5-NC-Pad13)") (class "Default")
      (node (ref "TR5") (pin "13") (pinfunction "NC_13") (pintype "passive"))
    )
    (net (code "42") (name "unconnected-(U12A-OSCVDD12-Pad3)") (class "Default")
      (node (ref "U12") (pin "3") (pinfunction "OSCVDD12_3") (pintype "passive+no_connect"))
    )
    (net (code "43") (name "unconnected-(U14-DAP-Pad9)") (class "Default")
      (node (ref "U14") (pin "9") (pinfunction "DAP_9") (pintype "power_in"))
    )
  )
)
